# SHAButton4.net
KiCad netlist of a schematic drawn in EAGLE
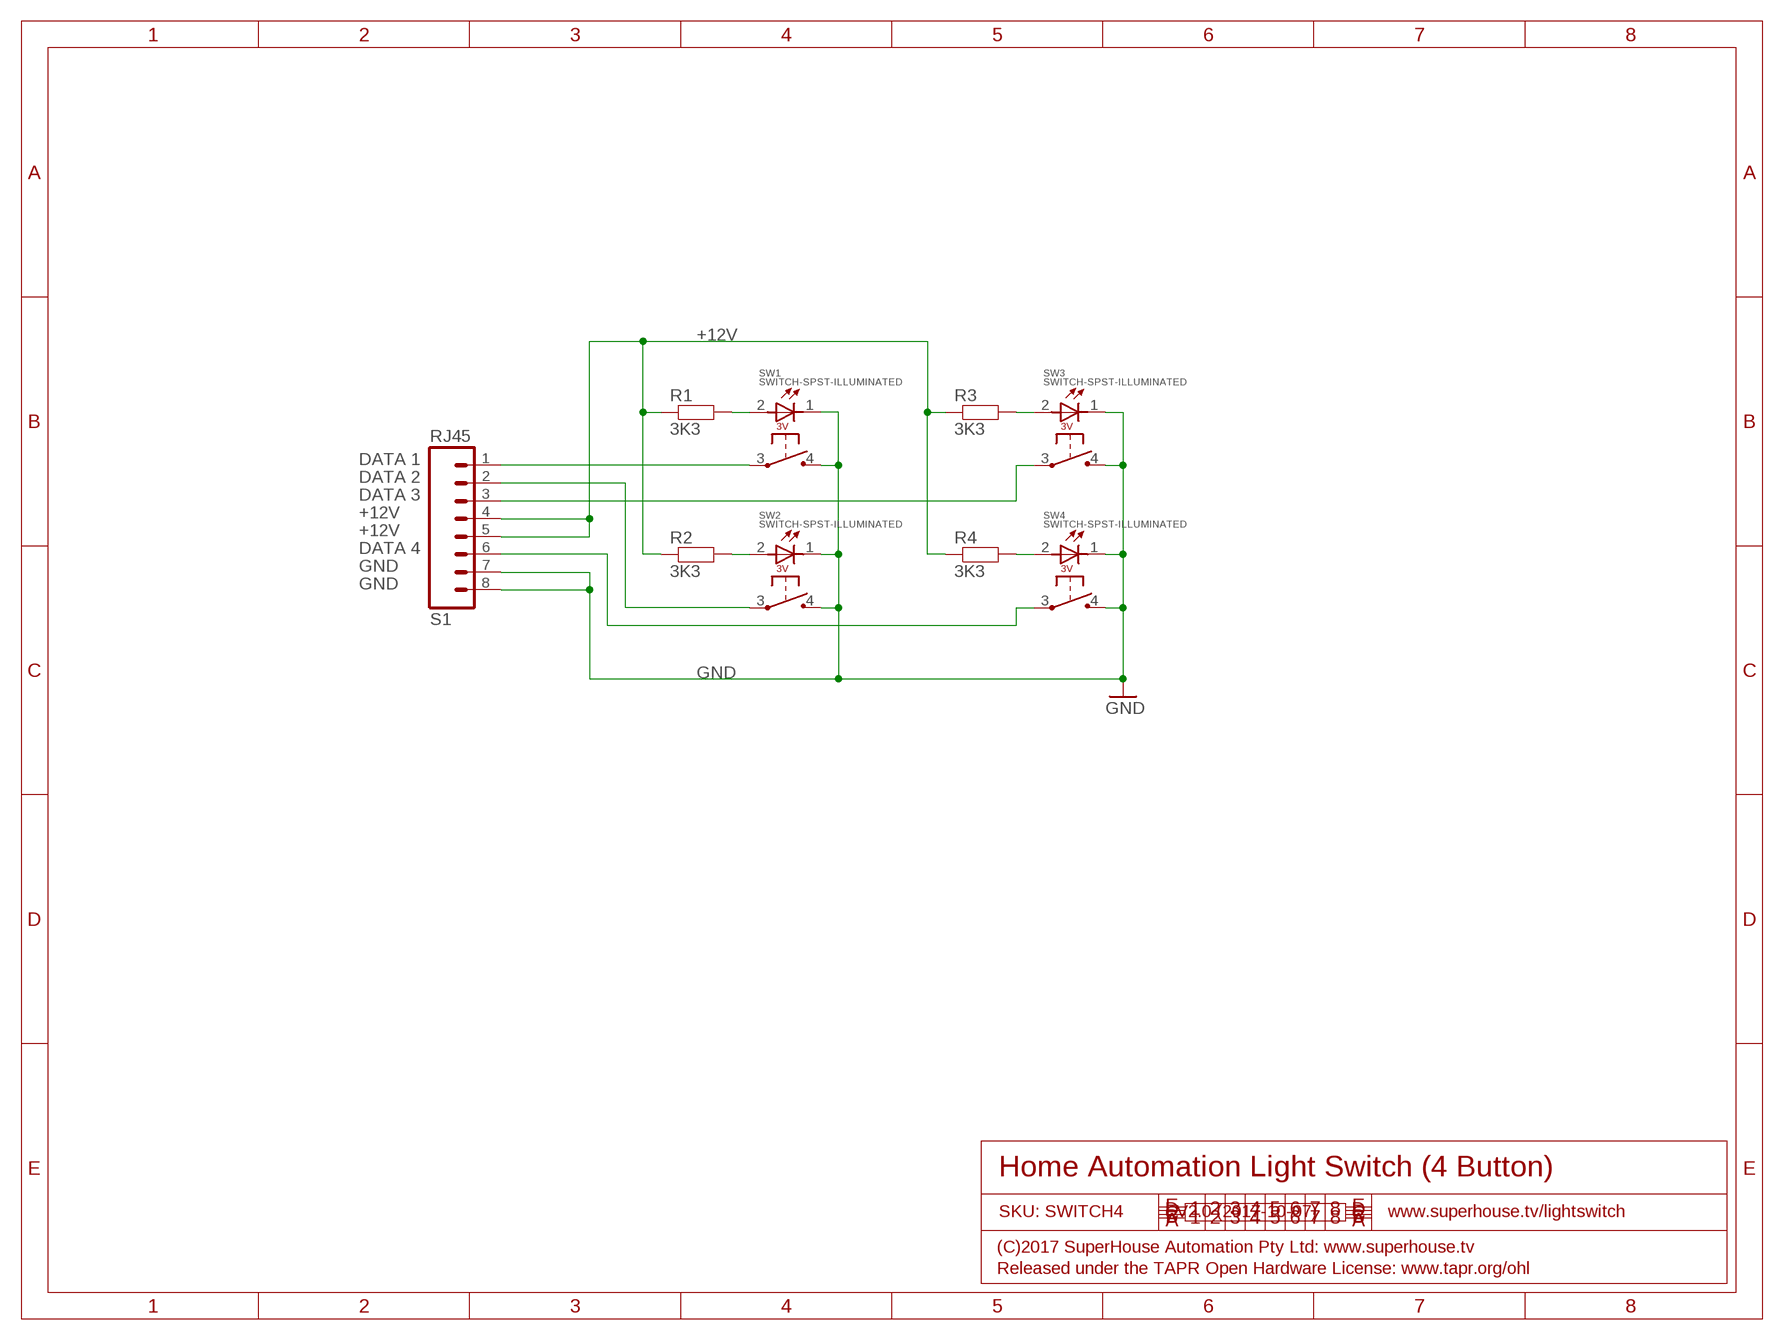
[diagram p0: schematic, sheet 1]

(export (version "E")
  (design (tool "Eeschema 10.0.6"))
  (components
    (comp (ref "R1")
      (value "3K3")
      (footprint "eagle-import:0603")
      (libsource (lib "eagle-import") (part "RESISTOR0603"))
    )
    (comp (ref "R2")
      (value "3K3")
      (footprint "eagle-import:0603")
      (libsource (lib "eagle-import") (part "RESISTOR0603"))
    )
    (comp (ref "R3")
      (value "3K3")
      (footprint "eagle-import:0603")
      (libsource (lib "eagle-import") (part "RESISTOR0603"))
    )
    (comp (ref "R4")
      (value "3K3")
      (footprint "eagle-import:0603")
      (libsource (lib "eagle-import") (part "RESISTOR0603"))
    )
    (comp (ref "S1")
      (value "RJ45")
      (footprint "eagle-import:RJ45")
      (libsource (lib "eagle-import") (part "RJ45"))
    )
    (comp (ref "SW1")
      (value "SWITCH-SPST-ILLUMINATED")
      (footprint "eagle-import:SWITCH-SPST-ILLUMINATED")
      (libsource (lib "eagle-import") (part "SWITCH-SPST-ILLUMINATED"))
    )
    (comp (ref "SW2")
      (value "SWITCH-SPST-ILLUMINATED")
      (footprint "eagle-import:SWITCH-SPST-ILLUMINATED")
      (libsource (lib "eagle-import") (part "SWITCH-SPST-ILLUMINATED"))
    )
    (comp (ref "SW3")
      (value "SWITCH-SPST-ILLUMINATED")
      (footprint "eagle-import:SWITCH-SPST-ILLUMINATED")
      (libsource (lib "eagle-import") (part "SWITCH-SPST-ILLUMINATED"))
    )
    (comp (ref "SW4")
      (value "SWITCH-SPST-ILLUMINATED")
      (footprint "eagle-import:SWITCH-SPST-ILLUMINATED")
      (libsource (lib "eagle-import") (part "SWITCH-SPST-ILLUMINATED"))
    )
  )
  (nets
    (net (code "1") (name "/+12V") (class "Default")
      (node (ref "R1") (pin "1") (pinfunction "1_1") (pintype "passive"))
      (node (ref "R2") (pin "1") (pinfunction "1_1") (pintype "passive"))
      (node (ref "R3") (pin "1") (pinfunction "1_1") (pintype "passive"))
      (node (ref "R4") (pin "1") (pinfunction "1_1") (pintype "passive"))
      (node (ref "S1") (pin "4") (pinfunction "4_4") (pintype "passive"))
      (node (ref "S1") (pin "5") (pinfunction "5_5") (pintype "passive"))
    )
    (net (code "2") (name "GND") (class "Default")
      (node (ref "S1") (pin "7") (pinfunction "7_7") (pintype "passive"))
      (node (ref "S1") (pin "8") (pinfunction "8_8") (pintype "passive"))
      (node (ref "SW1") (pin "1") (pinfunction "-_1") (pintype "passive"))
      (node (ref "SW1") (pin "4") (pinfunction "NO_4") (pintype "passive"))
      (node (ref "SW2") (pin "1") (pinfunction "-_1") (pintype "passive"))
      (node (ref "SW2") (pin "4") (pinfunction "NO_4") (pintype "passive"))
      (node (ref "SW3") (pin "1") (pinfunction "-_1") (pintype "passive"))
      (node (ref "SW3") (pin "4") (pinfunction "NO_4") (pintype "passive"))
      (node (ref "SW4") (pin "1") (pinfunction "-_1") (pintype "passive"))
      (node (ref "SW4") (pin "4") (pinfunction "NO_4") (pintype "passive"))
    )
    (net (code "3") (name "Net-(SW1-+)") (class "Default")
      (node (ref "R1") (pin "2") (pinfunction "2_2") (pintype "passive"))
      (node (ref "SW1") (pin "2") (pinfunction "+_2") (pintype "passive"))
    )
    (net (code "4") (name "Net-(SW1-COM)") (class "Default")
      (node (ref "S1") (pin "1") (pinfunction "1_1") (pintype "passive"))
      (node (ref "SW1") (pin "3") (pinfunction "COM_3") (pintype "passive"))
    )
    (net (code "5") (name "Net-(SW2-+)") (class "Default")
      (node (ref "R2") (pin "2") (pinfunction "2_2") (pintype "passive"))
      (node (ref "SW2") (pin "2") (pinfunction "+_2") (pintype "passive"))
    )
    (net (code "6") (name "Net-(SW2-COM)") (class "Default")
      (node (ref "S1") (pin "2") (pinfunction "2_2") (pintype "passive"))
      (node (ref "SW2") (pin "3") (pinfunction "COM_3") (pintype "passive"))
    )
    (net (code "7") (name "Net-(SW3-+)") (class "Default")
      (node (ref "R3") (pin "2") (pinfunction "2_2") (pintype "passive"))
      (node (ref "SW3") (pin "2") (pinfunction "+_2") (pintype "passive"))
    )
    (net (code "8") (name "Net-(SW3-COM)") (class "Default")
      (node (ref "S1") (pin "3") (pinfunction "3_3") (pintype "passive"))
      (node (ref "SW3") (pin "3") (pinfunction "COM_3") (pintype "passive"))
    )
    (net (code "9") (name "Net-(SW4-+)") (class "Default")
      (node (ref "R4") (pin "2") (pinfunction "2_2") (pintype "passive"))
      (node (ref "SW4") (pin "2") (pinfunction "+_2") (pintype "passive"))
    )
    (net (code "10") (name "Net-(SW4-COM)") (class "Default")
      (node (ref "S1") (pin "6") (pinfunction "6_6") (pintype "passive"))
      (node (ref "SW4") (pin "3") (pinfunction "COM_3") (pintype "passive"))
    )
  )
)
